# Hermit_Board_Rev_A3.net
KiCad netlist of a schematic drawn in EAGLE
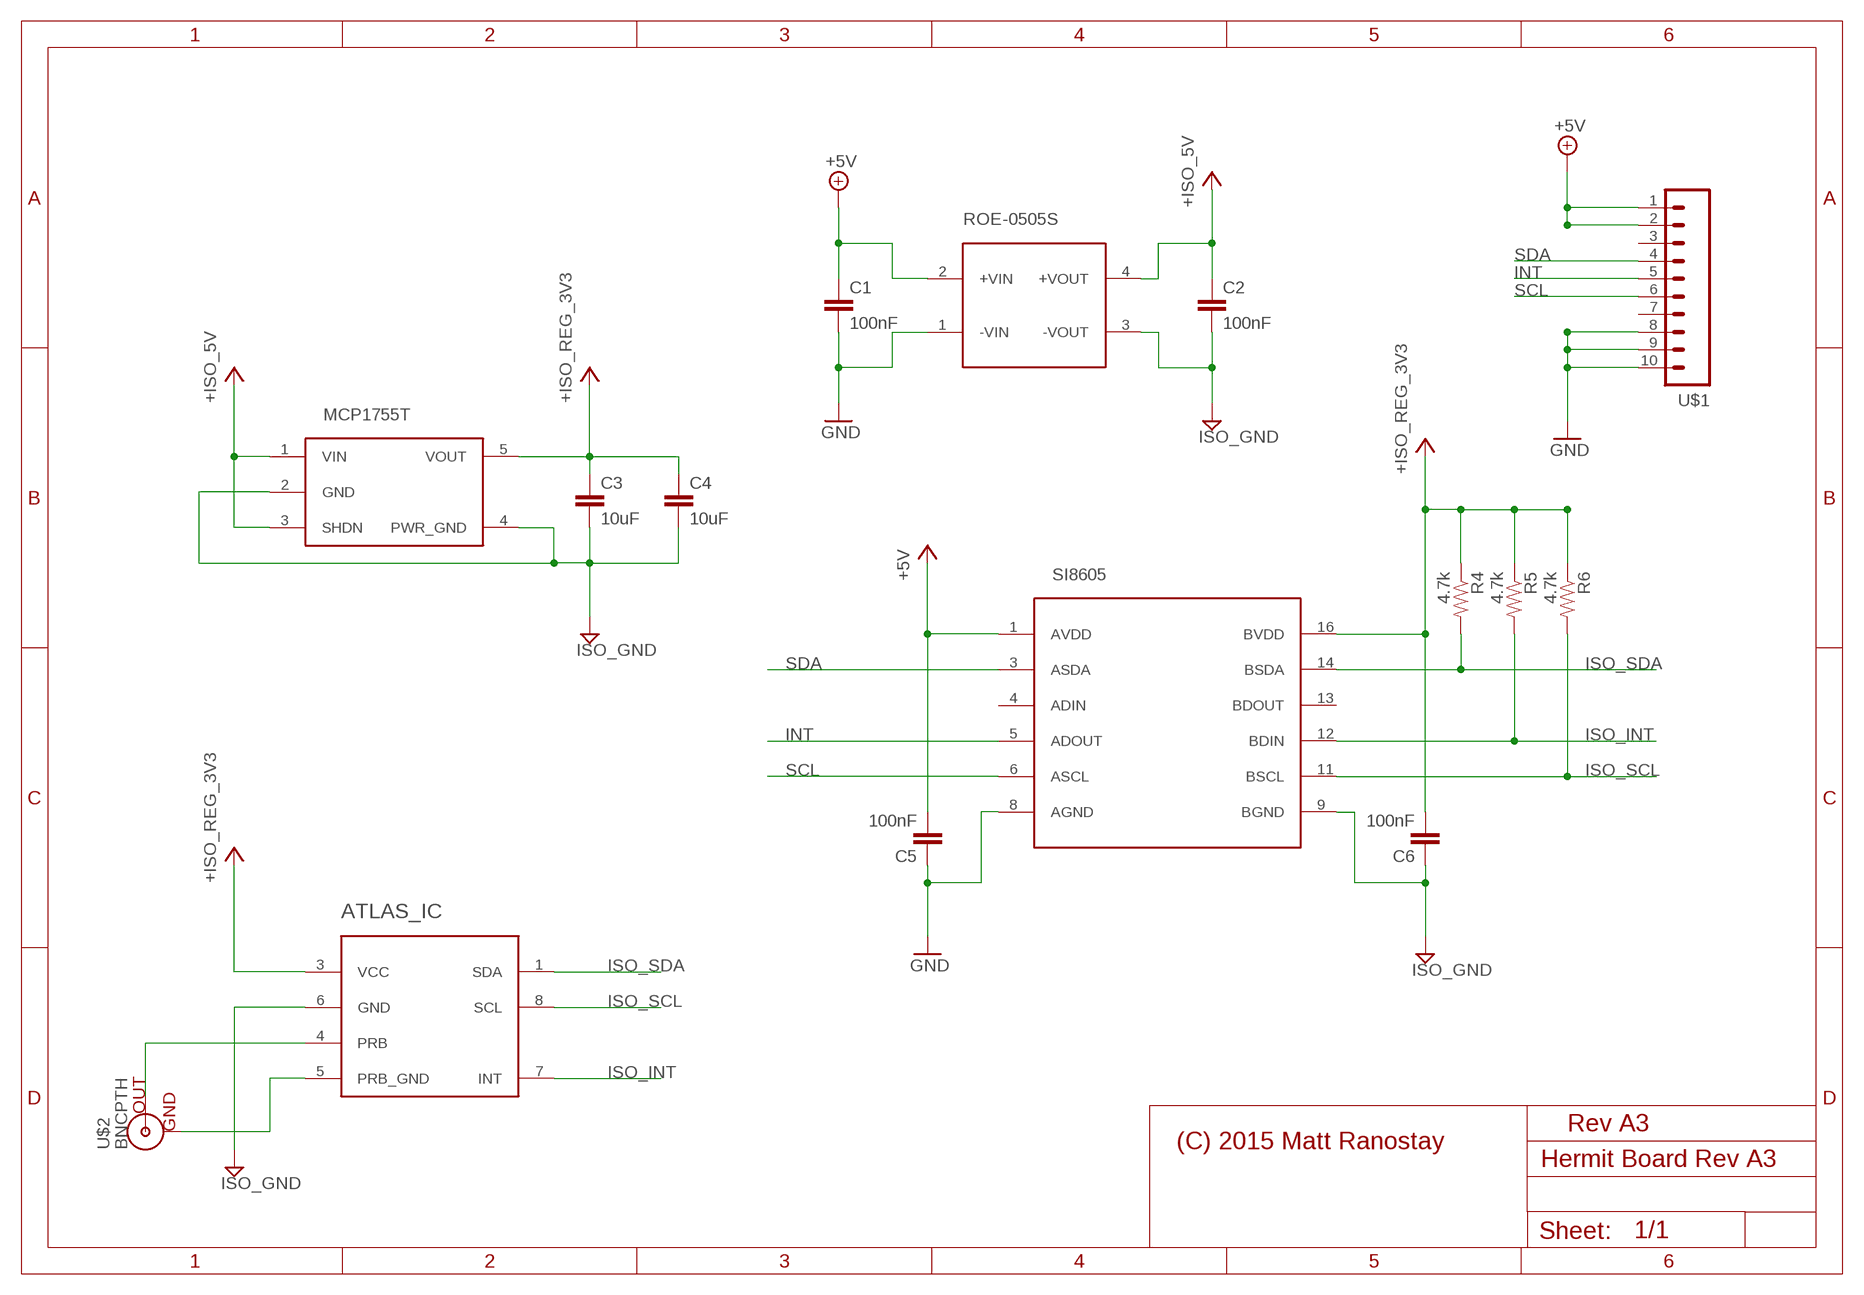
[diagram p0: schematic, sheet 1]

(export (version "E")
  (design (tool "Eeschema 10.0.6"))
  (components
    (comp (ref "ATLAS_IC")
      (value "ATLAS-OEM")
      (footprint "eagle-import:ATLAS-OEM")
      (libsource (lib "eagle-import") (part "ATLAS-OEM"))
    )
    (comp (ref "C1")
      (value "100nF")
      (footprint "eagle-import:0805")
      (libsource (lib "eagle-import") (part "CAP0805"))
    )
    (comp (ref "C2")
      (value "100nF")
      (footprint "eagle-import:0805")
      (libsource (lib "eagle-import") (part "CAP0805"))
    )
    (comp (ref "C3")
      (value "10uF")
      (footprint "eagle-import:0805")
      (libsource (lib "eagle-import") (part "CAP0805"))
    )
    (comp (ref "C4")
      (value "10uF")
      (footprint "eagle-import:0805")
      (libsource (lib "eagle-import") (part "CAP0805"))
    )
    (comp (ref "C5")
      (value "100nF")
      (footprint "eagle-import:0805")
      (libsource (lib "eagle-import") (part "CAP0805"))
    )
    (comp (ref "C6")
      (value "100nF")
      (footprint "eagle-import:0805")
      (libsource (lib "eagle-import") (part "CAP0805"))
    )
    (comp (ref "MCP1755T")
      (value "MCP1755T")
      (footprint "eagle-import:SOT-23-5")
      (libsource (lib "eagle-import") (part "MCP1755T"))
    )
    (comp (ref "R4")
      (value "4.7k")
      (footprint "eagle-import:0805")
      (libsource (lib "eagle-import") (part "RESISTOR0805-RES"))
    )
    (comp (ref "R5")
      (value "4.7k")
      (footprint "eagle-import:0805")
      (libsource (lib "eagle-import") (part "RESISTOR0805-RES"))
    )
    (comp (ref "R6")
      (value "4.7k")
      (footprint "eagle-import:0805")
      (libsource (lib "eagle-import") (part "RESISTOR0805-RES"))
    )
    (comp (ref "ROE-0505S")
      (value "ROE-0505S")
      (footprint "eagle-import:SIP4")
      (libsource (lib "eagle-import") (part "ROE-0505S"))
    )
    (comp (ref "SI8605")
      (value "SI8605")
      (footprint "eagle-import:SOIC16-1.27-10X3.9MM")
      (libsource (lib "eagle-import") (part "SI8605"))
    )
    (comp (ref "U$1")
      (value "M10SILK_FEMALE_PTH")
      (footprint "eagle-import:1X10")
      (libsource (lib "eagle-import") (part "M10SILK_FEMALE_PTH"))
    )
    (comp (ref "U$2")
      (value "BNCPTH")
      (footprint "eagle-import:BNC")
      (libsource (lib "eagle-import") (part "BNCPTH"))
    )
  )
  (nets
    (net (code "1") (name "+5V") (class "Default")
      (node (ref "C1") (pin "1") (pinfunction "1_1") (pintype "passive"))
      (node (ref "C5") (pin "2") (pinfunction "2_2") (pintype "passive"))
      (node (ref "ROE-0505S") (pin "2") (pinfunction "+VIN_2") (pintype "power_in"))
      (node (ref "SI8605") (pin "1") (pinfunction "AVDD_1") (pintype "power_in"))
      (node (ref "U$1") (pin "1") (pinfunction "1_1") (pintype "passive"))
      (node (ref "U$1") (pin "2") (pinfunction "2_2") (pintype "passive"))
    )
    (net (code "2") (name "+ISO_5V") (class "Default")
      (node (ref "C2") (pin "1") (pinfunction "1_1") (pintype "passive"))
      (node (ref "MCP1755T") (pin "1") (pinfunction "VIN_1") (pintype "power_in"))
      (node (ref "MCP1755T") (pin "3") (pinfunction "SHDN_3") (pintype "input"))
      (node (ref "ROE-0505S") (pin "4") (pinfunction "+VOUT_4") (pintype "power_in"))
    )
    (net (code "3") (name "+ISO_REG_3V3") (class "Default")
      (node (ref "ATLAS_IC") (pin "3") (pinfunction "VCC_3") (pintype "power_in"))
      (node (ref "C3") (pin "1") (pinfunction "1_1") (pintype "passive"))
      (node (ref "C4") (pin "1") (pinfunction "1_1") (pintype "passive"))
      (node (ref "C6") (pin "2") (pinfunction "2_2") (pintype "passive"))
      (node (ref "MCP1755T") (pin "5") (pinfunction "VOUT_5") (pintype "power_in"))
      (node (ref "R4") (pin "1") (pinfunction "1_1") (pintype "passive"))
      (node (ref "R5") (pin "1") (pinfunction "1_1") (pintype "passive"))
      (node (ref "R6") (pin "1") (pinfunction "1_1") (pintype "passive"))
      (node (ref "SI8605") (pin "16") (pinfunction "BVDD_16") (pintype "power_in"))
    )
    (net (code "4") (name "/INT") (class "Default")
      (node (ref "SI8605") (pin "5") (pinfunction "ADOUT_5") (pintype "output"))
      (node (ref "U$1") (pin "5") (pinfunction "5_5") (pintype "passive"))
    )
    (net (code "5") (name "/ISO_INT") (class "Default")
      (node (ref "ATLAS_IC") (pin "7") (pinfunction "INT_7") (pintype "output"))
      (node (ref "R5") (pin "2") (pinfunction "2_2") (pintype "passive"))
      (node (ref "SI8605") (pin "12") (pinfunction "BDIN_12") (pintype "input"))
    )
    (net (code "6") (name "/ISO_SCL") (class "Default")
      (node (ref "ATLAS_IC") (pin "8") (pinfunction "SCL_8") (pintype "bidirectional"))
      (node (ref "R6") (pin "2") (pinfunction "2_2") (pintype "passive"))
      (node (ref "SI8605") (pin "11") (pinfunction "BSCL_11") (pintype "bidirectional"))
    )
    (net (code "7") (name "/ISO_SDA") (class "Default")
      (node (ref "ATLAS_IC") (pin "1") (pinfunction "SDA_1") (pintype "bidirectional"))
      (node (ref "R4") (pin "2") (pinfunction "2_2") (pintype "passive"))
      (node (ref "SI8605") (pin "14") (pinfunction "BSDA_14") (pintype "bidirectional"))
    )
    (net (code "8") (name "/SCL") (class "Default")
      (node (ref "SI8605") (pin "6") (pinfunction "ASCL_6") (pintype "bidirectional"))
      (node (ref "U$1") (pin "6") (pinfunction "6_6") (pintype "passive"))
    )
    (net (code "9") (name "/SDA") (class "Default")
      (node (ref "SI8605") (pin "3") (pinfunction "ASDA_3") (pintype "bidirectional"))
      (node (ref "U$1") (pin "4") (pinfunction "4_4") (pintype "passive"))
    )
    (net (code "10") (name "GND") (class "Default")
      (node (ref "C1") (pin "2") (pinfunction "2_2") (pintype "passive"))
      (node (ref "C5") (pin "1") (pinfunction "1_1") (pintype "passive"))
      (node (ref "ROE-0505S") (pin "1") (pinfunction "-VIN_1") (pintype "power_in"))
      (node (ref "SI8605") (pin "8") (pinfunction "AGND_8") (pintype "power_in"))
      (node (ref "U$1") (pin "10") (pinfunction "10_10") (pintype "passive"))
      (node (ref "U$1") (pin "8") (pinfunction "8_8") (pintype "passive"))
      (node (ref "U$1") (pin "9") (pinfunction "9_9") (pintype "passive"))
    )
    (net (code "11") (name "ISO_GND") (class "Default")
      (node (ref "ATLAS_IC") (pin "6") (pinfunction "GND_6") (pintype "power_in"))
      (node (ref "C2") (pin "2") (pinfunction "2_2") (pintype "passive"))
      (node (ref "C3") (pin "2") (pinfunction "2_2") (pintype "passive"))
      (node (ref "C4") (pin "2") (pinfunction "2_2") (pintype "passive"))
      (node (ref "C6") (pin "1") (pinfunction "1_1") (pintype "passive"))
      (node (ref "MCP1755T") (pin "2") (pinfunction "GND_2") (pintype "power_in"))
      (node (ref "MCP1755T") (pin "4") (pinfunction "PWR_GND_4") (pintype "power_in"))
      (node (ref "ROE-0505S") (pin "3") (pinfunction "-VOUT_3") (pintype "power_in"))
      (node (ref "SI8605") (pin "9") (pinfunction "BGND_9") (pintype "power_in"))
    )
    (net (code "12") (name "Net-(ATLAS_IC-PRB)") (class "Default")
      (node (ref "ATLAS_IC") (pin "4") (pinfunction "PRB_4") (pintype "input"))
      (node (ref "U$2") (pin "S") (pinfunction "OUT_S") (pintype "bidirectional"))
    )
    (net (code "13") (name "Net-(ATLAS_IC-PRB_GND)") (class "Default")
      (node (ref "ATLAS_IC") (pin "5") (pinfunction "PRB_GND_5") (pintype "power_in"))
      (node (ref "U$2") (pin "GND") (pinfunction "GND_GND") (pintype "bidirectional"))
    )
    (net (code "14") (name "unconnected-(SI8605-ADIN-Pad4)") (class "Default")
      (node (ref "SI8605") (pin "4") (pinfunction "ADIN_4") (pintype "input"))
    )
    (net (code "15") (name "unconnected-(SI8605-BDOUT-Pad13)") (class "Default")
      (node (ref "SI8605") (pin "13") (pinfunction "BDOUT_13") (pintype "output"))
    )
    (net (code "16") (name "unconnected-(U$1-Pad3)") (class "Default")
      (node (ref "U$1") (pin "3") (pinfunction "3_3") (pintype "passive"))
    )
    (net (code "17") (name "unconnected-(U$1-Pad7)") (class "Default")
      (node (ref "U$1") (pin "7") (pinfunction "7_7") (pintype "passive"))
    )
  )
)
